# ECE_362_mini_project1.net
KiCad netlist of a schematic drawn in EAGLE
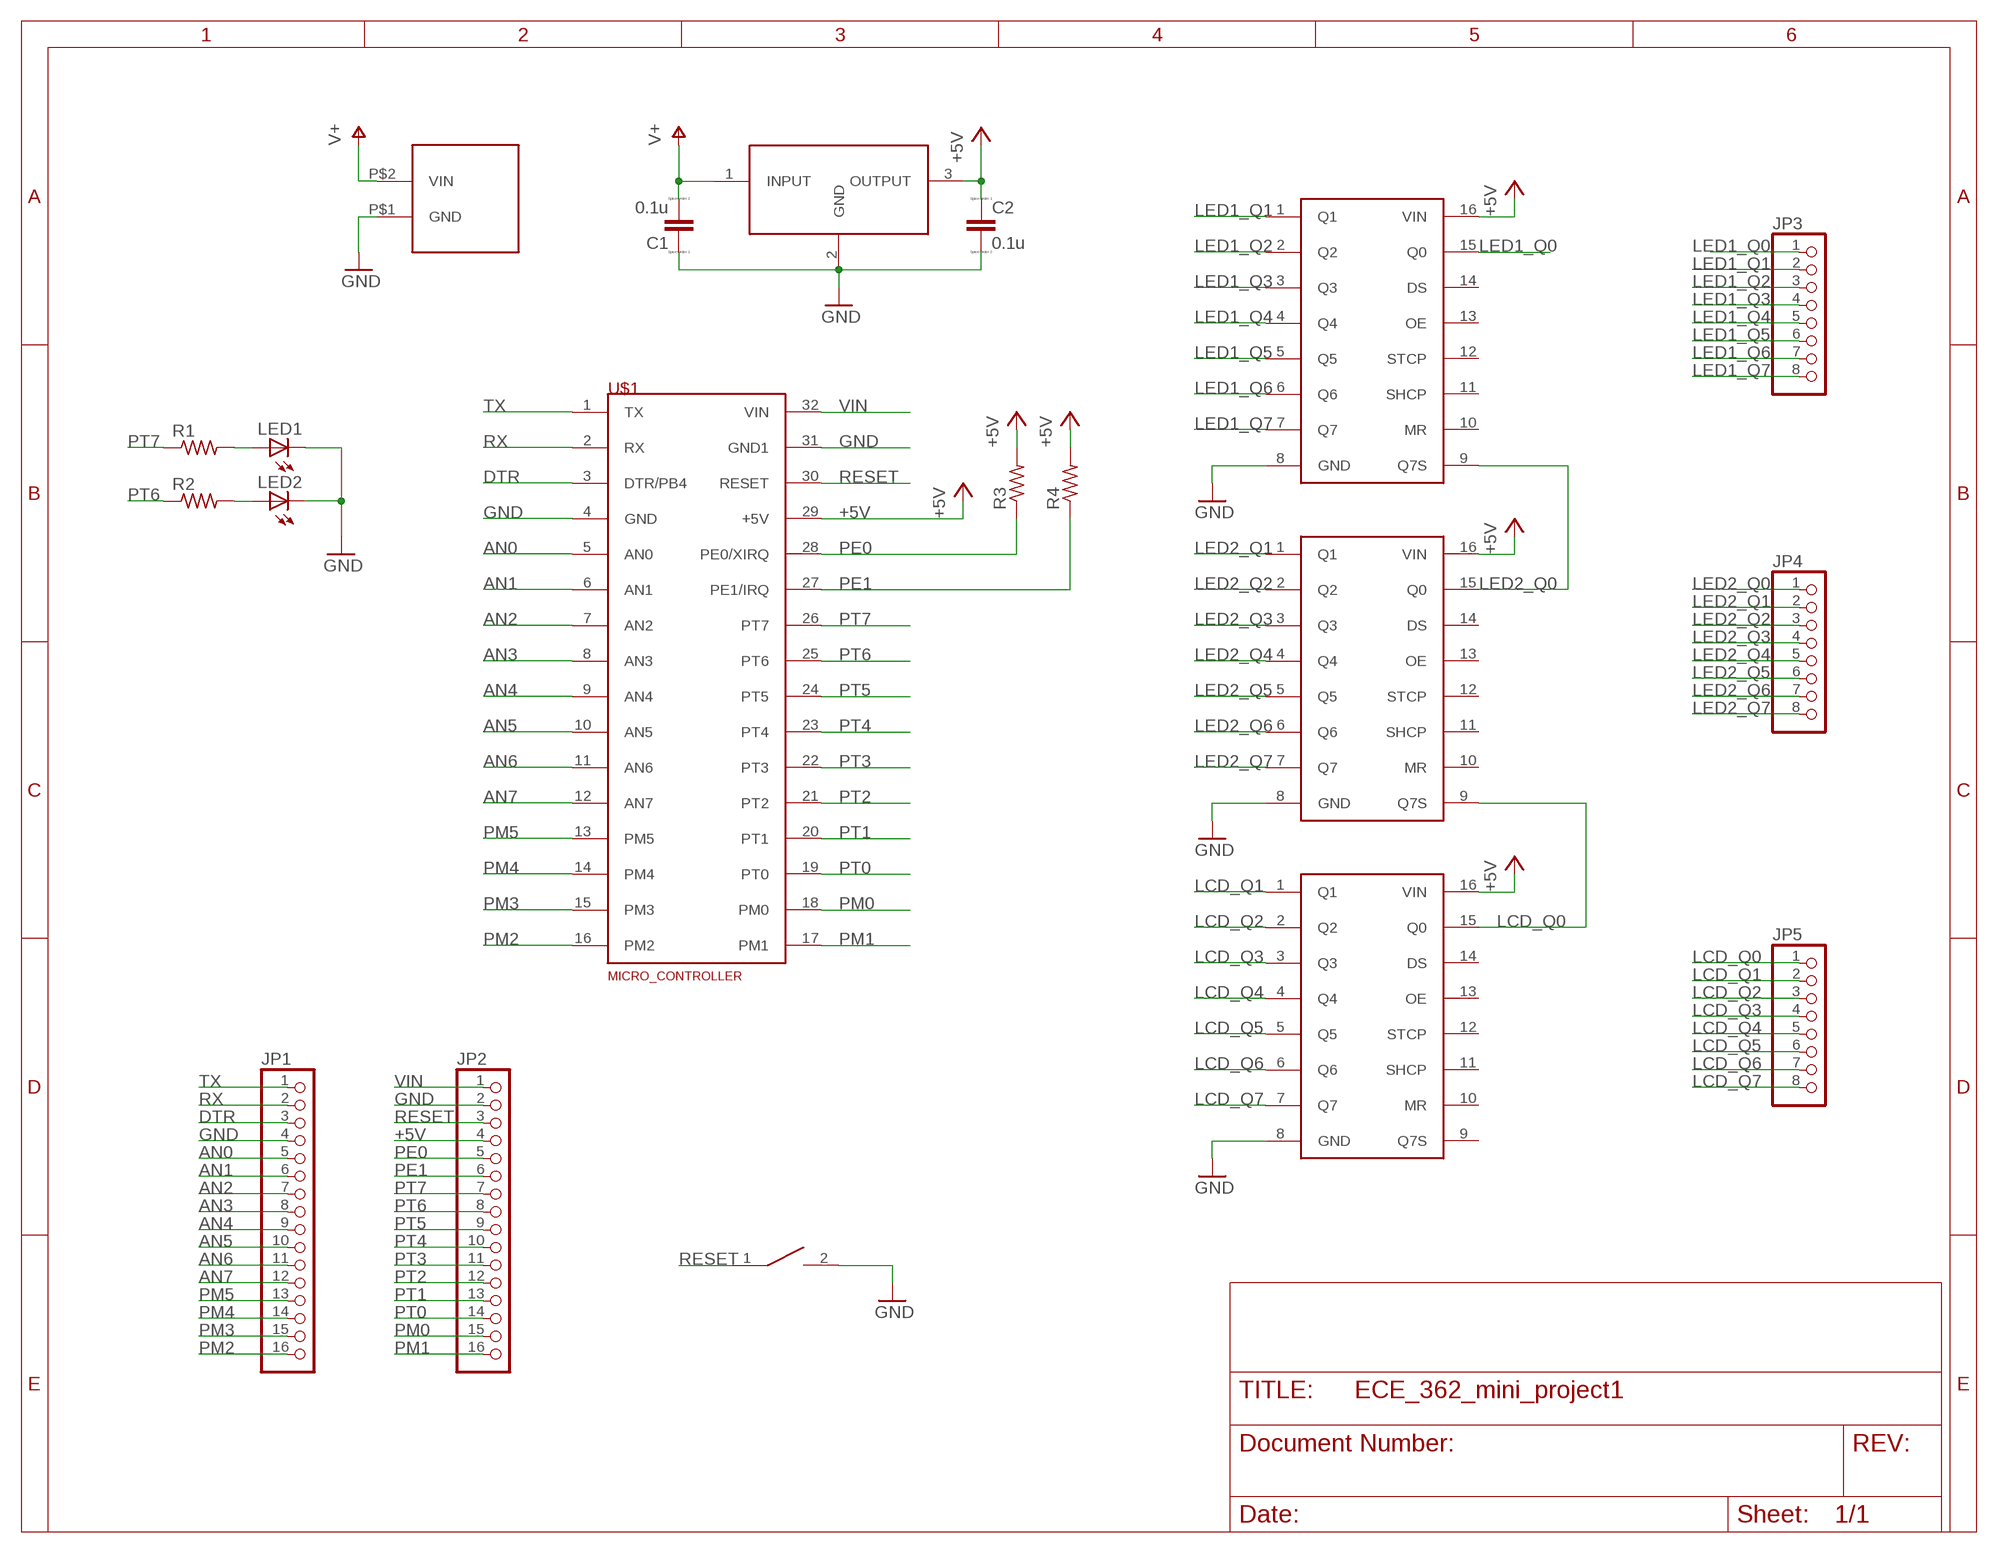
[diagram p0: schematic, sheet 1]

(export (version "E")
  (design (tool "Eeschema 10.0.6"))
  (components
    (comp (ref "BOOT_SW")
      (value "SWITCH")
      (footprint "eagle-import:SW_2512")
      (libsource (lib "eagle-import") (part "SWITCH"))
    )
    (comp (ref "C1")
      (value "0.1u")
      (footprint "eagle-import:C0603")
      (libsource (lib "eagle-import") (part "CC0603"))
    )
    (comp (ref "C2")
      (value "0.1u")
      (footprint "eagle-import:C0603")
      (libsource (lib "eagle-import") (part "CC0603"))
    )
    (comp (ref "JP1")
      (value "PINHD-1X16")
      (footprint "eagle-import:1X16")
      (libsource (lib "eagle-import") (part "PINHD-1X16"))
    )
    (comp (ref "JP2")
      (value "PINHD-1X16")
      (footprint "eagle-import:1X16")
      (libsource (lib "eagle-import") (part "PINHD-1X16"))
    )
    (comp (ref "JP3")
      (value "PINHD-1X8")
      (footprint "eagle-import:1X08")
      (libsource (lib "eagle-import") (part "PINHD-1X8"))
    )
    (comp (ref "JP4")
      (value "PINHD-1X8")
      (footprint "eagle-import:1X08")
      (libsource (lib "eagle-import") (part "PINHD-1X8"))
    )
    (comp (ref "JP5")
      (value "PINHD-1X8")
      (footprint "eagle-import:1X08")
      (libsource (lib "eagle-import") (part "PINHD-1X8"))
    )
    (comp (ref "LED1")
      (value "LEDCHIPLED_0603")
      (footprint "eagle-import:CHIPLED_0603")
      (libsource (lib "eagle-import") (part "LEDCHIPLED_0603"))
    )
    (comp (ref "LED2")
      (value "LEDCHIPLED_0603")
      (footprint "eagle-import:CHIPLED_0603")
      (libsource (lib "eagle-import") (part "LEDCHIPLED_0603"))
    )
    (comp (ref "R1")
      (value "R-US_R0603")
      (footprint "eagle-import:R0603")
      (libsource (lib "eagle-import") (part "R-US_R0603"))
    )
    (comp (ref "R2")
      (value "R-US_R0603")
      (footprint "eagle-import:R0603")
      (libsource (lib "eagle-import") (part "R-US_R0603"))
    )
    (comp (ref "R3")
      (value "R-US_R0603")
      (footprint "eagle-import:R0603")
      (libsource (lib "eagle-import") (part "R-US_R0603"))
    )
    (comp (ref "R4")
      (value "R-US_R0603")
      (footprint "eagle-import:R0603")
      (libsource (lib "eagle-import") (part "R-US_R0603"))
    )
    (comp (ref "U$1")
      (value "MICRO_CONTROLLER")
      (footprint "eagle-import:MICRO_CONTROLLER")
      (libsource (lib "eagle-import") (part "MICRO_CONTROLLER"))
    )
    (comp (ref "U$2")
      (value "SHIFT_REGISTER")
      (footprint "eagle-import:N5")
      (libsource (lib "eagle-import") (part "SHIFT_REGISTER"))
    )
    (comp (ref "U$3")
      (value "XT60")
      (footprint "eagle-import:XT60")
      (libsource (lib "eagle-import") (part "XT60"))
    )
    (comp (ref "U$4")
      (value "SHIFT_REGISTER")
      (footprint "eagle-import:N5")
      (libsource (lib "eagle-import") (part "SHIFT_REGISTER"))
    )
    (comp (ref "U$5")
      (value "SHIFT_REGISTER")
      (footprint "eagle-import:N5")
      (libsource (lib "eagle-import") (part "SHIFT_REGISTER"))
    )
    (comp (ref "U$6")
      (value "L7805CV")
      (footprint "eagle-import:L7805CV")
      (libsource (lib "eagle-import") (part "L7805CV"))
    )
  )
  (nets
    (net (code "1") (name "+5V") (class "Default")
      (node (ref "C2") (pin "1") (pinfunction "1_1") (pintype "passive"))
      (node (ref "JP2") (pin "4") (pinfunction "4_4") (pintype "passive"))
      (node (ref "R3") (pin "2") (pinfunction "2_2") (pintype "passive"))
      (node (ref "R4") (pin "2") (pinfunction "2_2") (pintype "passive"))
      (node (ref "U$1") (pin "29") (pinfunction "+5V_29") (pintype "bidirectional"))
      (node (ref "U$2") (pin "16") (pinfunction "VIN_16") (pintype "bidirectional"))
      (node (ref "U$4") (pin "16") (pinfunction "VIN_16") (pintype "bidirectional"))
      (node (ref "U$5") (pin "16") (pinfunction "VIN_16") (pintype "bidirectional"))
      (node (ref "U$6") (pin "3") (pinfunction "OUTPUT_3") (pintype "bidirectional"))
    )
    (net (code "2") (name "/AN0") (class "Default")
      (node (ref "JP1") (pin "5") (pinfunction "5_5") (pintype "passive"))
      (node (ref "U$1") (pin "5") (pinfunction "AN0_5") (pintype "bidirectional"))
    )
    (net (code "3") (name "/AN1") (class "Default")
      (node (ref "JP1") (pin "6") (pinfunction "6_6") (pintype "passive"))
      (node (ref "U$1") (pin "6") (pinfunction "AN1_6") (pintype "bidirectional"))
    )
    (net (code "4") (name "/AN2") (class "Default")
      (node (ref "JP1") (pin "7") (pinfunction "7_7") (pintype "passive"))
      (node (ref "U$1") (pin "7") (pinfunction "AN2_7") (pintype "bidirectional"))
    )
    (net (code "5") (name "/AN3") (class "Default")
      (node (ref "JP1") (pin "8") (pinfunction "8_8") (pintype "passive"))
      (node (ref "U$1") (pin "8") (pinfunction "AN3_8") (pintype "bidirectional"))
    )
    (net (code "6") (name "/AN4") (class "Default")
      (node (ref "JP1") (pin "9") (pinfunction "9_9") (pintype "passive"))
      (node (ref "U$1") (pin "9") (pinfunction "AN4_9") (pintype "bidirectional"))
    )
    (net (code "7") (name "/AN5") (class "Default")
      (node (ref "JP1") (pin "10") (pinfunction "10_10") (pintype "passive"))
      (node (ref "U$1") (pin "10") (pinfunction "AN5_10") (pintype "bidirectional"))
    )
    (net (code "8") (name "/AN6") (class "Default")
      (node (ref "JP1") (pin "11") (pinfunction "11_11") (pintype "passive"))
      (node (ref "U$1") (pin "11") (pinfunction "AN6_11") (pintype "bidirectional"))
    )
    (net (code "9") (name "/AN7") (class "Default")
      (node (ref "JP1") (pin "12") (pinfunction "12_12") (pintype "passive"))
      (node (ref "U$1") (pin "12") (pinfunction "AN7_12") (pintype "bidirectional"))
    )
    (net (code "10") (name "/DTR") (class "Default")
      (node (ref "JP1") (pin "3") (pinfunction "3_3") (pintype "passive"))
      (node (ref "U$1") (pin "3") (pinfunction "DTR/PB4_3") (pintype "bidirectional"))
    )
    (net (code "11") (name "/LCD_Q0") (class "Default")
      (node (ref "JP5") (pin "1") (pinfunction "1_1") (pintype "passive"))
      (node (ref "U$4") (pin "9") (pinfunction "Q7S_9") (pintype "bidirectional"))
      (node (ref "U$5") (pin "15") (pinfunction "Q0_15") (pintype "bidirectional"))
    )
    (net (code "12") (name "/LCD_Q1") (class "Default")
      (node (ref "JP5") (pin "2") (pinfunction "2_2") (pintype "passive"))
      (node (ref "U$5") (pin "1") (pinfunction "Q1_1") (pintype "bidirectional"))
    )
    (net (code "13") (name "/LCD_Q2") (class "Default")
      (node (ref "JP5") (pin "3") (pinfunction "3_3") (pintype "passive"))
      (node (ref "U$5") (pin "2") (pinfunction "Q2_2") (pintype "bidirectional"))
    )
    (net (code "14") (name "/LCD_Q3") (class "Default")
      (node (ref "JP5") (pin "4") (pinfunction "4_4") (pintype "passive"))
      (node (ref "U$5") (pin "3") (pinfunction "Q3_3") (pintype "bidirectional"))
    )
    (net (code "15") (name "/LCD_Q4") (class "Default")
      (node (ref "JP5") (pin "5") (pinfunction "5_5") (pintype "passive"))
      (node (ref "U$5") (pin "4") (pinfunction "Q4_4") (pintype "bidirectional"))
    )
    (net (code "16") (name "/LCD_Q5") (class "Default")
      (node (ref "JP5") (pin "6") (pinfunction "6_6") (pintype "passive"))
      (node (ref "U$5") (pin "5") (pinfunction "Q5_5") (pintype "bidirectional"))
    )
    (net (code "17") (name "/LCD_Q6") (class "Default")
      (node (ref "JP5") (pin "7") (pinfunction "7_7") (pintype "passive"))
      (node (ref "U$5") (pin "6") (pinfunction "Q6_6") (pintype "bidirectional"))
    )
    (net (code "18") (name "/LCD_Q7") (class "Default")
      (node (ref "JP5") (pin "8") (pinfunction "8_8") (pintype "passive"))
      (node (ref "U$5") (pin "7") (pinfunction "Q7_7") (pintype "bidirectional"))
    )
    (net (code "19") (name "/LED1_Q0") (class "Default")
      (node (ref "JP3") (pin "1") (pinfunction "1_1") (pintype "passive"))
      (node (ref "U$2") (pin "15") (pinfunction "Q0_15") (pintype "bidirectional"))
    )
    (net (code "20") (name "/LED1_Q1") (class "Default")
      (node (ref "JP3") (pin "2") (pinfunction "2_2") (pintype "passive"))
      (node (ref "U$2") (pin "1") (pinfunction "Q1_1") (pintype "bidirectional"))
    )
    (net (code "21") (name "/LED1_Q2") (class "Default")
      (node (ref "JP3") (pin "3") (pinfunction "3_3") (pintype "passive"))
      (node (ref "U$2") (pin "2") (pinfunction "Q2_2") (pintype "bidirectional"))
    )
    (net (code "22") (name "/LED1_Q3") (class "Default")
      (node (ref "JP3") (pin "4") (pinfunction "4_4") (pintype "passive"))
      (node (ref "U$2") (pin "3") (pinfunction "Q3_3") (pintype "bidirectional"))
    )
    (net (code "23") (name "/LED1_Q4") (class "Default")
      (node (ref "JP3") (pin "5") (pinfunction "5_5") (pintype "passive"))
      (node (ref "U$2") (pin "4") (pinfunction "Q4_4") (pintype "bidirectional"))
    )
    (net (code "24") (name "/LED1_Q5") (class "Default")
      (node (ref "JP3") (pin "6") (pinfunction "6_6") (pintype "passive"))
      (node (ref "U$2") (pin "5") (pinfunction "Q5_5") (pintype "bidirectional"))
    )
    (net (code "25") (name "/LED1_Q6") (class "Default")
      (node (ref "JP3") (pin "7") (pinfunction "7_7") (pintype "passive"))
      (node (ref "U$2") (pin "6") (pinfunction "Q6_6") (pintype "bidirectional"))
    )
    (net (code "26") (name "/LED1_Q7") (class "Default")
      (node (ref "JP3") (pin "8") (pinfunction "8_8") (pintype "passive"))
      (node (ref "U$2") (pin "7") (pinfunction "Q7_7") (pintype "bidirectional"))
    )
    (net (code "27") (name "/LED2_Q0") (class "Default")
      (node (ref "JP4") (pin "1") (pinfunction "1_1") (pintype "passive"))
      (node (ref "U$2") (pin "9") (pinfunction "Q7S_9") (pintype "bidirectional"))
      (node (ref "U$4") (pin "15") (pinfunction "Q0_15") (pintype "bidirectional"))
    )
    (net (code "28") (name "/LED2_Q1") (class "Default")
      (node (ref "JP4") (pin "2") (pinfunction "2_2") (pintype "passive"))
      (node (ref "U$4") (pin "1") (pinfunction "Q1_1") (pintype "bidirectional"))
    )
    (net (code "29") (name "/LED2_Q2") (class "Default")
      (node (ref "JP4") (pin "3") (pinfunction "3_3") (pintype "passive"))
      (node (ref "U$4") (pin "2") (pinfunction "Q2_2") (pintype "bidirectional"))
    )
    (net (code "30") (name "/LED2_Q3") (class "Default")
      (node (ref "JP4") (pin "4") (pinfunction "4_4") (pintype "passive"))
      (node (ref "U$4") (pin "3") (pinfunction "Q3_3") (pintype "bidirectional"))
    )
    (net (code "31") (name "/LED2_Q4") (class "Default")
      (node (ref "JP4") (pin "5") (pinfunction "5_5") (pintype "passive"))
      (node (ref "U$4") (pin "4") (pinfunction "Q4_4") (pintype "bidirectional"))
    )
    (net (code "32") (name "/LED2_Q5") (class "Default")
      (node (ref "JP4") (pin "6") (pinfunction "6_6") (pintype "passive"))
      (node (ref "U$4") (pin "5") (pinfunction "Q5_5") (pintype "bidirectional"))
    )
    (net (code "33") (name "/LED2_Q6") (class "Default")
      (node (ref "JP4") (pin "7") (pinfunction "7_7") (pintype "passive"))
      (node (ref "U$4") (pin "6") (pinfunction "Q6_6") (pintype "bidirectional"))
    )
    (net (code "34") (name "/LED2_Q7") (class "Default")
      (node (ref "JP4") (pin "8") (pinfunction "8_8") (pintype "passive"))
      (node (ref "U$4") (pin "7") (pinfunction "Q7_7") (pintype "bidirectional"))
    )
    (net (code "35") (name "/PE0") (class "Default")
      (node (ref "JP2") (pin "5") (pinfunction "5_5") (pintype "passive"))
      (node (ref "R3") (pin "1") (pinfunction "1_1") (pintype "passive"))
      (node (ref "U$1") (pin "28") (pinfunction "PE0/XIRQ_28") (pintype "bidirectional"))
    )
    (net (code "36") (name "/PE1") (class "Default")
      (node (ref "JP2") (pin "6") (pinfunction "6_6") (pintype "passive"))
      (node (ref "R4") (pin "1") (pinfunction "1_1") (pintype "passive"))
      (node (ref "U$1") (pin "27") (pinfunction "PE1/IRQ_27") (pintype "bidirectional"))
    )
    (net (code "37") (name "/PM0") (class "Default")
      (node (ref "JP2") (pin "15") (pinfunction "15_15") (pintype "passive"))
      (node (ref "U$1") (pin "18") (pinfunction "PM0_18") (pintype "bidirectional"))
    )
    (net (code "38") (name "/PM1") (class "Default")
      (node (ref "JP2") (pin "16") (pinfunction "16_16") (pintype "passive"))
      (node (ref "U$1") (pin "17") (pinfunction "PM1_17") (pintype "bidirectional"))
    )
    (net (code "39") (name "/PM2") (class "Default")
      (node (ref "JP1") (pin "16") (pinfunction "16_16") (pintype "passive"))
      (node (ref "U$1") (pin "16") (pinfunction "PM2_16") (pintype "bidirectional"))
    )
    (net (code "40") (name "/PM3") (class "Default")
      (node (ref "JP1") (pin "15") (pinfunction "15_15") (pintype "passive"))
      (node (ref "U$1") (pin "15") (pinfunction "PM3_15") (pintype "bidirectional"))
    )
    (net (code "41") (name "/PM4") (class "Default")
      (node (ref "JP1") (pin "14") (pinfunction "14_14") (pintype "passive"))
      (node (ref "U$1") (pin "14") (pinfunction "PM4_14") (pintype "bidirectional"))
    )
    (net (code "42") (name "/PM5") (class "Default")
      (node (ref "JP1") (pin "13") (pinfunction "13_13") (pintype "passive"))
      (node (ref "U$1") (pin "13") (pinfunction "PM5_13") (pintype "bidirectional"))
    )
    (net (code "43") (name "/PT0") (class "Default")
      (node (ref "JP2") (pin "14") (pinfunction "14_14") (pintype "passive"))
      (node (ref "U$1") (pin "19") (pinfunction "PT0_19") (pintype "bidirectional"))
    )
    (net (code "44") (name "/PT1") (class "Default")
      (node (ref "JP2") (pin "13") (pinfunction "13_13") (pintype "passive"))
      (node (ref "U$1") (pin "20") (pinfunction "PT1_20") (pintype "bidirectional"))
    )
    (net (code "45") (name "/PT2") (class "Default")
      (node (ref "JP2") (pin "12") (pinfunction "12_12") (pintype "passive"))
      (node (ref "U$1") (pin "21") (pinfunction "PT2_21") (pintype "bidirectional"))
    )
    (net (code "46") (name "/PT3") (class "Default")
      (node (ref "JP2") (pin "11") (pinfunction "11_11") (pintype "passive"))
      (node (ref "U$1") (pin "22") (pinfunction "PT3_22") (pintype "bidirectional"))
    )
    (net (code "47") (name "/PT4") (class "Default")
      (node (ref "JP2") (pin "10") (pinfunction "10_10") (pintype "passive"))
      (node (ref "U$1") (pin "23") (pinfunction "PT4_23") (pintype "bidirectional"))
    )
    (net (code "48") (name "/PT5") (class "Default")
      (node (ref "JP2") (pin "9") (pinfunction "9_9") (pintype "passive"))
      (node (ref "U$1") (pin "24") (pinfunction "PT5_24") (pintype "bidirectional"))
    )
    (net (code "49") (name "/PT6") (class "Default")
      (node (ref "JP2") (pin "8") (pinfunction "8_8") (pintype "passive"))
      (node (ref "R2") (pin "1") (pinfunction "1_1") (pintype "passive"))
      (node (ref "U$1") (pin "25") (pinfunction "PT6_25") (pintype "bidirectional"))
    )
    (net (code "50") (name "/PT7") (class "Default")
      (node (ref "JP2") (pin "7") (pinfunction "7_7") (pintype "passive"))
      (node (ref "R1") (pin "1") (pinfunction "1_1") (pintype "passive"))
      (node (ref "U$1") (pin "26") (pinfunction "PT7_26") (pintype "bidirectional"))
    )
    (net (code "51") (name "/RESET") (class "Default")
      (node (ref "BOOT_SW") (pin "1") (pinfunction "P$1_1") (pintype "bidirectional"))
      (node (ref "JP2") (pin "3") (pinfunction "3_3") (pintype "passive"))
      (node (ref "U$1") (pin "30") (pinfunction "RESET_30") (pintype "bidirectional"))
    )
    (net (code "52") (name "/RX") (class "Default")
      (node (ref "JP1") (pin "2") (pinfunction "2_2") (pintype "passive"))
      (node (ref "U$1") (pin "2") (pinfunction "RX_2") (pintype "bidirectional"))
    )
    (net (code "53") (name "/TX") (class "Default")
      (node (ref "JP1") (pin "1") (pinfunction "1_1") (pintype "passive"))
      (node (ref "U$1") (pin "1") (pinfunction "TX_1") (pintype "bidirectional"))
    )
    (net (code "54") (name "/VIN") (class "Default")
      (node (ref "JP2") (pin "1") (pinfunction "1_1") (pintype "passive"))
      (node (ref "U$1") (pin "32") (pinfunction "VIN_32") (pintype "bidirectional"))
    )
    (net (code "55") (name "GND") (class "Default")
      (node (ref "BOOT_SW") (pin "2") (pinfunction "P$2_2") (pintype "bidirectional"))
      (node (ref "C1") (pin "1") (pinfunction "1_1") (pintype "passive"))
      (node (ref "C2") (pin "2") (pinfunction "2_2") (pintype "passive"))
      (node (ref "JP1") (pin "4") (pinfunction "4_4") (pintype "passive"))
      (node (ref "JP2") (pin "2") (pinfunction "2_2") (pintype "passive"))
      (node (ref "LED1") (pin "C") (pinfunction "C_C") (pintype "passive"))
      (node (ref "LED2") (pin "C") (pinfunction "C_C") (pintype "passive"))
      (node (ref "U$1") (pin "31") (pinfunction "GND1_31") (pintype "bidirectional"))
      (node (ref "U$1") (pin "4") (pinfunction "GND_4") (pintype "bidirectional"))
      (node (ref "U$2") (pin "8") (pinfunction "GND_8") (pintype "bidirectional"))
      (node (ref "U$3") (pin "P$1") (pinfunction "GND_P$1") (pintype "bidirectional"))
      (node (ref "U$4") (pin "8") (pinfunction "GND_8") (pintype "bidirectional"))
      (node (ref "U$5") (pin "8") (pinfunction "GND_8") (pintype "bidirectional"))
      (node (ref "U$6") (pin "2") (pinfunction "GND_2") (pintype "bidirectional"))
    )
    (net (code "56") (name "Net-(LED1-PadA)") (class "Default")
      (node (ref "LED1") (pin "A") (pinfunction "A_A") (pintype "passive"))
      (node (ref "R1") (pin "2") (pinfunction "2_2") (pintype "passive"))
    )
    (net (code "57") (name "Net-(LED2-PadA)") (class "Default")
      (node (ref "LED2") (pin "A") (pinfunction "A_A") (pintype "passive"))
      (node (ref "R2") (pin "2") (pinfunction "2_2") (pintype "passive"))
    )
    (net (code "58") (name "V+") (class "Default")
      (node (ref "C1") (pin "2") (pinfunction "2_2") (pintype "passive"))
      (node (ref "U$3") (pin "P$2") (pinfunction "VIN_P$2") (pintype "bidirectional"))
      (node (ref "U$6") (pin "1") (pinfunction "INPUT_1") (pintype "bidirectional"))
    )
    (net (code "59") (name "unconnected-(U$2-DS-Pad14)") (class "Default")
      (node (ref "U$2") (pin "14") (pinfunction "DS_14") (pintype "bidirectional"))
    )
    (net (code "60") (name "unconnected-(U$2-MR-Pad10)") (class "Default")
      (node (ref "U$2") (pin "10") (pinfunction "MR_10") (pintype "bidirectional"))
    )
    (net (code "61") (name "unconnected-(U$2-OE-Pad13)") (class "Default")
      (node (ref "U$2") (pin "13") (pinfunction "OE_13") (pintype "bidirectional"))
    )
    (net (code "62") (name "unconnected-(U$2-SHCP-Pad11)") (class "Default")
      (node (ref "U$2") (pin "11") (pinfunction "SHCP_11") (pintype "bidirectional"))
    )
    (net (code "63") (name "unconnected-(U$2-STCP-Pad12)") (class "Default")
      (node (ref "U$2") (pin "12") (pinfunction "STCP_12") (pintype "bidirectional"))
    )
    (net (code "64") (name "unconnected-(U$4-DS-Pad14)") (class "Default")
      (node (ref "U$4") (pin "14") (pinfunction "DS_14") (pintype "bidirectional"))
    )
    (net (code "65") (name "unconnected-(U$4-MR-Pad10)") (class "Default")
      (node (ref "U$4") (pin "10") (pinfunction "MR_10") (pintype "bidirectional"))
    )
    (net (code "66") (name "unconnected-(U$4-OE-Pad13)") (class "Default")
      (node (ref "U$4") (pin "13") (pinfunction "OE_13") (pintype "bidirectional"))
    )
    (net (code "67") (name "unconnected-(U$4-SHCP-Pad11)") (class "Default")
      (node (ref "U$4") (pin "11") (pinfunction "SHCP_11") (pintype "bidirectional"))
    )
    (net (code "68") (name "unconnected-(U$4-STCP-Pad12)") (class "Default")
      (node (ref "U$4") (pin "12") (pinfunction "STCP_12") (pintype "bidirectional"))
    )
    (net (code "69") (name "unconnected-(U$5-DS-Pad14)") (class "Default")
      (node (ref "U$5") (pin "14") (pinfunction "DS_14") (pintype "bidirectional"))
    )
    (net (code "70") (name "unconnected-(U$5-MR-Pad10)") (class "Default")
      (node (ref "U$5") (pin "10") (pinfunction "MR_10") (pintype "bidirectional"))
    )
    (net (code "71") (name "unconnected-(U$5-OE-Pad13)") (class "Default")
      (node (ref "U$5") (pin "13") (pinfunction "OE_13") (pintype "bidirectional"))
    )
    (net (code "72") (name "unconnected-(U$5-Q7S-Pad9)") (class "Default")
      (node (ref "U$5") (pin "9") (pinfunction "Q7S_9") (pintype "bidirectional"))
    )
    (net (code "73") (name "unconnected-(U$5-SHCP-Pad11)") (class "Default")
      (node (ref "U$5") (pin "11") (pinfunction "SHCP_11") (pintype "bidirectional"))
    )
    (net (code "74") (name "unconnected-(U$5-STCP-Pad12)") (class "Default")
      (node (ref "U$5") (pin "12") (pinfunction "STCP_12") (pintype "bidirectional"))
    )
  )
)
